# Input.net
KiCad netlist of a schematic drawn in Altium Designer
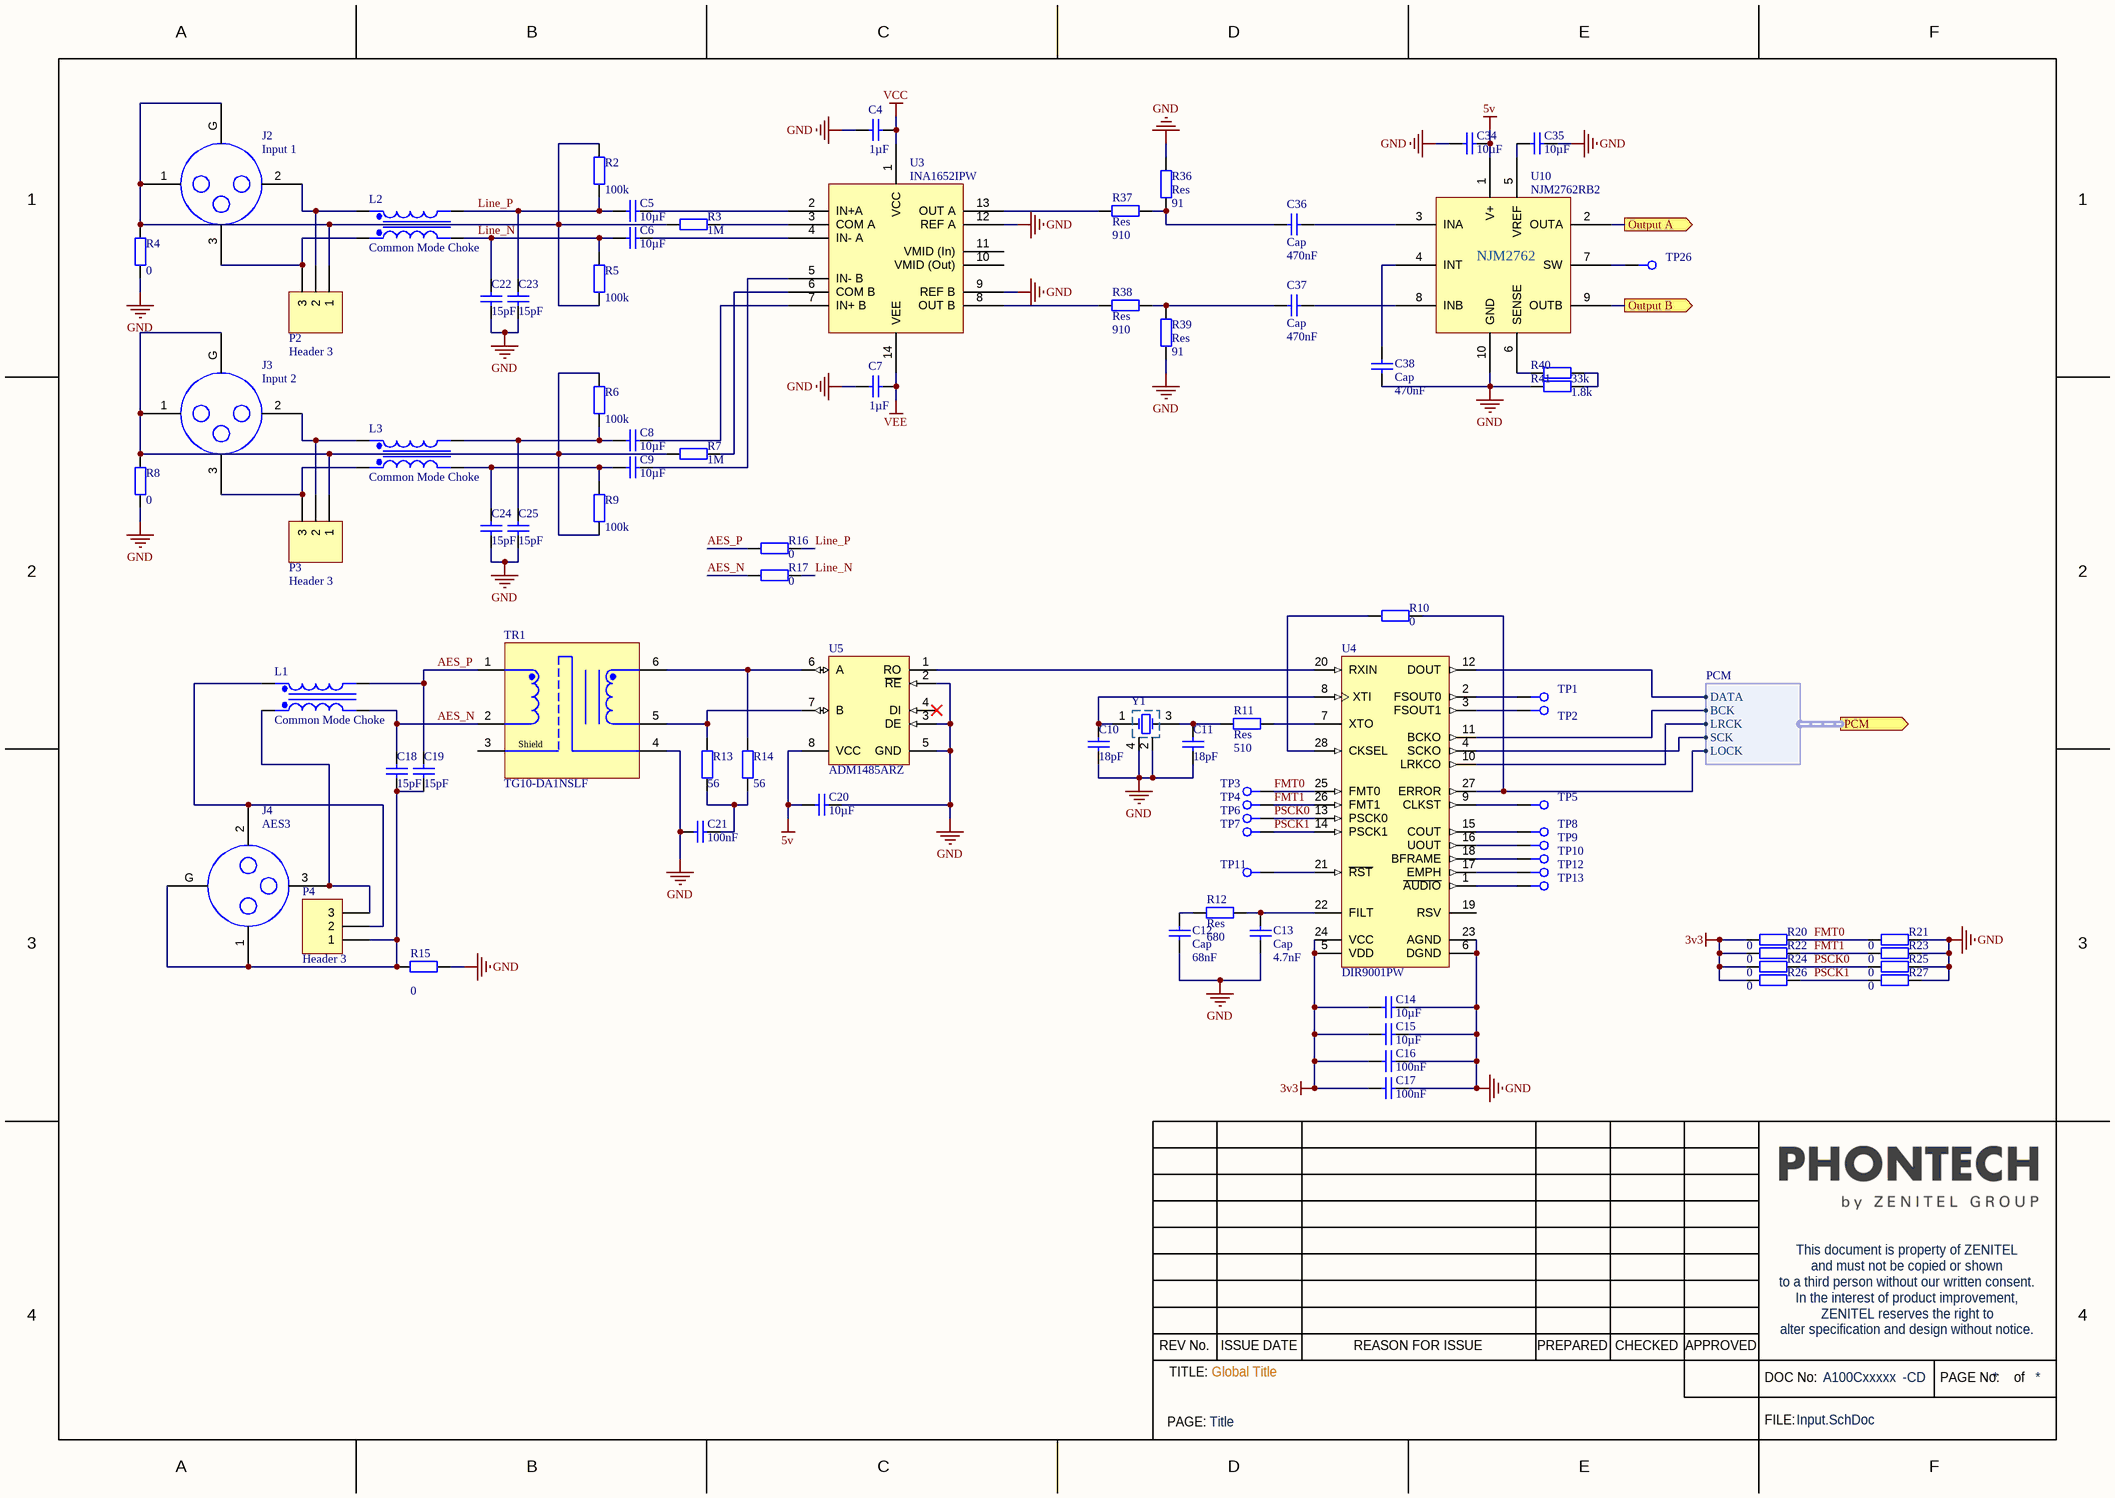
[diagram p0: Input.SchDoc]

(export (version "E")
  (design (tool "Eeschema 10.0.6"))
  (components
    (comp (ref "C4")
      (value "1µF")
      (footprint "CAPC3225N")
      (description "Chip cap 1uF 50v X7R 1210")
      (fields (field (name "TOLERANCE") "10%") (field (name "ZENITEL PARTNUMBER") "4000084277"))
      (libsource (lib "Zenitel Concord PRO Vault") (part "Capacitor-IEC"))
    )
    (comp (ref "C5")
      (value "10µF")
      (footprint "CAPC5750N")
      (description "10UF, 100V, X7S, 2220")
      (fields (field (name "TOLERANCE") "100%") (field (name "VOLTAGE") "100V"))
      (libsource (lib "Zenitel Concord PRO Vault") (part "Capacitor-IEC"))
    )
    (comp (ref "C6")
      (value "10µF")
      (footprint "CAPC5750N")
      (description "10UF, 100V, X7S, 2220")
      (fields (field (name "TOLERANCE") "100%") (field (name "VOLTAGE") "100V"))
      (libsource (lib "Zenitel Concord PRO Vault") (part "Capacitor-IEC"))
    )
    (comp (ref "C7")
      (value "1µF")
      (footprint "CAPC3225N")
      (description "Chip cap 1uF 50v X7R 1210")
      (fields (field (name "TOLERANCE") "10%") (field (name "ZENITEL PARTNUMBER") "4000084277"))
      (libsource (lib "Zenitel Concord PRO Vault") (part "Capacitor-IEC"))
    )
    (comp (ref "C8")
      (value "10µF")
      (footprint "CAPC5750N")
      (description "10UF, 100V, X7S, 2220")
      (fields (field (name "TOLERANCE") "100%") (field (name "VOLTAGE") "100V"))
      (libsource (lib "Zenitel Concord PRO Vault") (part "Capacitor-IEC"))
    )
    (comp (ref "C9")
      (value "10µF")
      (footprint "CAPC5750N")
      (description "10UF, 100V, X7S, 2220")
      (fields (field (name "TOLERANCE") "100%") (field (name "VOLTAGE") "100V"))
      (libsource (lib "Zenitel Concord PRO Vault") (part "Capacitor-IEC"))
    )
    (comp (ref "C10")
      (value "18pF")
      (footprint "CAPC1005X56X25NL10T15")
      (description "Chip cap 18p 50V - 0402")
      (fields (field (name "TOLERANCE") "5%") (field (name "ZENITEL PARTNUMBER") "4000080916"))
      (libsource (lib "Zenitel Concord PRO Vault") (part "Capacitor-IEC"))
    )
    (comp (ref "C11")
      (value "18pF")
      (footprint "CAPC1005X56X25NL10T15")
      (description "Chip cap 18p 50V - 0402")
      (fields (field (name "TOLERANCE") "5%") (field (name "ZENITEL PARTNUMBER") "4000080916"))
      (libsource (lib "Zenitel Concord PRO Vault") (part "Capacitor-IEC"))
    )
    (comp (ref "C12")
      (value "Cap")
      (footprint "CAPC1005X56X25NL10T15")
      (description "Chip cap 68n 10V - 0402")
      (fields
        (field (name "ALTIUM_VALUE") "68nF")
        (field (name "VOLTAGE") "10V")
        (field (name "TOLERANCE") "100%")
      )
      (libsource (lib "Zenitel Concord PRO Vault") (part "Capacitor-IEC"))
    )
    (comp (ref "C13")
      (value "Cap")
      (footprint "CAPC1005X56X25NL10T15")
      (description "Chip cap 4700p 50V - 0402")
      (fields
        (field (name "ALTIUM_VALUE") "4.7nF")
        (field (name "ZENITEL PARTNUMBER") "4000080940")
        (field (name "VOLTAGE") "50V")
      )
      (libsource (lib "Zenitel Concord PRO Vault") (part "Capacitor-IEC"))
    )
    (comp (ref "C14")
      (value "10µF")
      (footprint "CAPC2013X140X50NL20T25")
      (description "CR0805 10u 10V X7R 10% h=1.25mm")
      (fields (field (name "TOLERANCE") "10%") (field (name "VOLTAGE") "10V"))
      (libsource (lib "Zenitel Concord PRO Vault") (part "Capacitor-IEC"))
    )
    (comp (ref "C15")
      (value "10µF")
      (footprint "CAPC2013X140X50NL20T25")
      (description "CR0805 10u 10V X7R 10% h=1.25mm")
      (fields (field (name "TOLERANCE") "10%") (field (name "VOLTAGE") "10V"))
      (libsource (lib "Zenitel Concord PRO Vault") (part "Capacitor-IEC"))
    )
    (comp (ref "C16")
      (value "100nF")
      (footprint "CAPC1005X56X25NL10T15")
      (description "Chip cap  100n 10V - 0402  X7R")
      (fields (field (name "TOLERANCE") "10%") (field (name "VOLTAGE") "10V"))
      (libsource (lib "Zenitel Concord PRO Vault") (part "Capacitor-IEC"))
    )
    (comp (ref "C17")
      (value "100nF")
      (footprint "CAPC1005X56X25NL10T15")
      (description "Chip cap  100n 10V - 0402  X7R")
      (fields (field (name "TOLERANCE") "10%") (field (name "VOLTAGE") "10V"))
      (libsource (lib "Zenitel Concord PRO Vault") (part "Capacitor-IEC"))
    )
    (comp (ref "C18")
      (value "15pF")
      (footprint "CAPC1005X56X25NL10T15")
      (description "Chip cap 15pF 50V NP0 - 0402")
      (fields (field (name "TOLERANCE") "1%") (field (name "ZENITEL PARTNUMBER") "EFSMD17120"))
      (libsource (lib "Zenitel Concord PRO Vault") (part "Capacitor-IEC"))
    )
    (comp (ref "C19")
      (value "15pF")
      (footprint "CAPC1005X56X25NL10T15")
      (description "Chip cap 15pF 50V NP0 - 0402")
      (fields (field (name "TOLERANCE") "1%") (field (name "ZENITEL PARTNUMBER") "EFSMD17120"))
      (libsource (lib "Zenitel Concord PRO Vault") (part "Capacitor-IEC"))
    )
    (comp (ref "C20")
      (value "10µF")
      (footprint "CAPC2013X140X50NL20T25")
      (description "CR0805 10u 10V X7R 10% h=1.25mm")
      (fields (field (name "TOLERANCE") "10%") (field (name "VOLTAGE") "10V"))
      (libsource (lib "Zenitel Concord PRO Vault") (part "Capacitor-IEC"))
    )
    (comp (ref "C21")
      (value "100nF")
      (footprint "CAPC1608X90X35NL15T15")
      (description "Chip cap  100n 50V X7R - 0603")
      (fields (field (name "ZENITEL PARTNUMBER") "4000084734") (field (name "TOLERANCE") "10%"))
      (libsource (lib "Zenitel Concord PRO Vault") (part "Capacitor-IEC"))
    )
    (comp (ref "C22")
      (value "15pF")
      (footprint "CAPC1005X56X25NL10T15")
      (description "Chip cap 15pF 50V NP0 - 0402")
      (fields (field (name "TOLERANCE") "1%") (field (name "ZENITEL PARTNUMBER") "EFSMD17120"))
      (libsource (lib "Zenitel Concord PRO Vault") (part "Capacitor-IEC"))
    )
    (comp (ref "C23")
      (value "15pF")
      (footprint "CAPC1005X56X25NL10T15")
      (description "Chip cap 15pF 50V NP0 - 0402")
      (fields (field (name "TOLERANCE") "1%") (field (name "ZENITEL PARTNUMBER") "EFSMD17120"))
      (libsource (lib "Zenitel Concord PRO Vault") (part "Capacitor-IEC"))
    )
    (comp (ref "C24")
      (value "15pF")
      (footprint "CAPC1005X56X25NL10T15")
      (description "Chip cap 15pF 50V NP0 - 0402")
      (fields (field (name "TOLERANCE") "1%") (field (name "ZENITEL PARTNUMBER") "EFSMD17120"))
      (libsource (lib "Zenitel Concord PRO Vault") (part "Capacitor-IEC"))
    )
    (comp (ref "C25")
      (value "15pF")
      (footprint "CAPC1005X56X25NL10T15")
      (description "Chip cap 15pF 50V NP0 - 0402")
      (fields (field (name "TOLERANCE") "1%") (field (name "ZENITEL PARTNUMBER") "EFSMD17120"))
      (libsource (lib "Zenitel Concord PRO Vault") (part "Capacitor-IEC"))
    )
    (comp (ref "C34")
      (value "10µF")
      (footprint "CAPC2013X140X50NL20T25")
      (description "CR0805 10u 10V X7R 10% h=1.25mm")
      (fields (field (name "TOLERANCE") "10%") (field (name "VOLTAGE") "10V"))
      (libsource (lib "Zenitel Concord PRO Vault") (part "Capacitor-IEC"))
    )
    (comp (ref "C35")
      (value "10µF")
      (footprint "CAPC2013X140X50NL20T25")
      (description "CR0805 10u 10V X7R 10% h=1.25mm")
      (fields (field (name "TOLERANCE") "10%") (field (name "VOLTAGE") "10V"))
      (libsource (lib "Zenitel Concord PRO Vault") (part "Capacitor-IEC"))
    )
    (comp (ref "C36")
      (value "Cap")
      (footprint "CAPC1608X90X35NL15T15")
      (description "Chip cap 470nF 16V X7R - 0603")
      (fields
        (field (name "ALTIUM_VALUE") "470nF")
        (field (name "VOLTAGE") "16V")
        (field (name "ZENITEL PARTNUMBER") "EFSMD16664")
      )
      (libsource (lib "Zenitel Concord PRO Vault") (part "Capacitor-IEC"))
    )
    (comp (ref "C37")
      (value "Cap")
      (footprint "CAPC1608X90X35NL15T15")
      (description "Chip cap 470nF 16V X7R - 0603")
      (fields
        (field (name "ALTIUM_VALUE") "470nF")
        (field (name "VOLTAGE") "16V")
        (field (name "ZENITEL PARTNUMBER") "EFSMD16664")
      )
      (libsource (lib "Zenitel Concord PRO Vault") (part "Capacitor-IEC"))
    )
    (comp (ref "C38")
      (value "Cap")
      (footprint "CAPC1608X90X35NL15T15")
      (description "Chip cap 470nF 16V X7R - 0603")
      (fields
        (field (name "ALTIUM_VALUE") "470nF")
        (field (name "VOLTAGE") "16V")
        (field (name "ZENITEL PARTNUMBER") "EFSMD16664")
      )
      (libsource (lib "Zenitel Concord PRO Vault") (part "Capacitor-IEC"))
    )
    (comp (ref "J2")
      (value "Input 1")
      (footprint "NC3FAH2")
      (description "NC3FAH2 3pole female XLR 90deg")
      (fields (field (name "ZENITEL PARTNUMBER") "4000083398"))
      (libsource (lib "Zenitel Concord PRO Vault") (part "NC3FAH2"))
    )
    (comp (ref "J3")
      (value "Input 2")
      (footprint "NC3FAH2")
      (description "NC3FAH2 3pole female XLR 90deg")
      (fields (field (name "ZENITEL PARTNUMBER") "4000083398"))
      (libsource (lib "Zenitel Concord PRO Vault") (part "NC3FAH2"))
    )
    (comp (ref "J4")
      (value "AES3")
      (footprint "NC3FAH2")
      (description "NC3FAH2 3pole female XLR 90deg")
      (fields (field (name "ZENITEL PARTNUMBER") "4000083398"))
      (libsource (lib "Zenitel Concord PRO Vault") (part "NC3FAH2"))
    )
    (comp (ref "L1")
      (value "Common Mode Choke")
      (footprint "WE-CNSW-1206")
      (description "WE-CNSW SMD Common Mode Line Filter")
      (fields (field (name "ZENITEL PARTNUMBER") "4000086128"))
      (libsource (lib "Zenitel Concord PRO Vault") (part "Common Mode Choke"))
    )
    (comp (ref "L2")
      (value "Common Mode Choke")
      (footprint "WE-CNSW-1206")
      (description "WE-CNSW SMD Common Mode Line Filter")
      (fields (field (name "ZENITEL PARTNUMBER") "4000086128"))
      (libsource (lib "Zenitel Concord PRO Vault") (part "Common Mode Choke"))
    )
    (comp (ref "L3")
      (value "Common Mode Choke")
      (footprint "WE-CNSW-1206")
      (description "WE-CNSW SMD Common Mode Line Filter")
      (fields (field (name "ZENITEL PARTNUMBER") "4000086128"))
      (libsource (lib "Zenitel Concord PRO Vault") (part "Common Mode Choke"))
    )
    (comp (ref "P2")
      (value "Header 3")
      (footprint "MTA-100-3P")
      (description "MTA-100-3P 3-pin header")
      (fields (field (name "ZENITEL PARTNUMBER") "4000085467"))
      (libsource (lib "Zenitel Concord PRO Vault") (part "Header 3"))
    )
    (comp (ref "P3")
      (value "Header 3")
      (footprint "MTA-100-3P")
      (description "MTA-100-3P 3-pin header")
      (fields (field (name "ZENITEL PARTNUMBER") "4000085467"))
      (libsource (lib "Zenitel Concord PRO Vault") (part "Header 3"))
    )
    (comp (ref "P4")
      (value "Header 3")
      (footprint "MTA-100-3P")
      (description "MTA-100-3P 3-pin header")
      (fields (field (name "ZENITEL PARTNUMBER") "4000085467"))
      (libsource (lib "") (part "Header 3_1"))
    )
    (comp (ref "R2")
      (value "100k")
      (footprint "RESC1005X40X25NL05T05")
      (description "Chip resistor 100K - 0402")
      (fields (field (name "POWER") "62.5mW") (field (name "ZENITEL PARTNUMBER") "4000081112"))
      (libsource (lib "Zenitel Concord PRO Vault") (part "Resistor-IEC"))
    )
    (comp (ref "R3")
      (value "1M")
      (footprint "RESC1005X40X25NL05T05")
      (description "Chip resistor 1M 1% - 0402")
      (fields (field (name "VOLTAGE") "50V") (field (name "POWER") "62.5mW"))
      (libsource (lib "") (part "Resistor-IEC_1"))
    )
    (comp (ref "R4")
      (value "0")
      (footprint "RESC3216X60X45NL10T20")
      (description "0R 1206")
      (fields (field (name "ZENITEL PARTNUMBER") "4000085059") (field (name "POWER") "250mW"))
      (libsource (lib "Zenitel Concord PRO Vault") (part "Resistor-IEC"))
    )
    (comp (ref "R5")
      (value "100k")
      (footprint "RESC1005X40X25NL05T05")
      (description "Chip resistor 100K - 0402")
      (fields (field (name "POWER") "62.5mW") (field (name "ZENITEL PARTNUMBER") "4000081112"))
      (libsource (lib "Zenitel Concord PRO Vault") (part "Resistor-IEC"))
    )
    (comp (ref "R6")
      (value "100k")
      (footprint "RESC1005X40X25NL05T05")
      (description "Chip resistor 100K - 0402")
      (fields (field (name "POWER") "62.5mW") (field (name "ZENITEL PARTNUMBER") "4000081112"))
      (libsource (lib "Zenitel Concord PRO Vault") (part "Resistor-IEC"))
    )
    (comp (ref "R7")
      (value "1M")
      (footprint "RESC1005X40X25NL05T05")
      (description "Chip resistor 1M 1% - 0402")
      (fields (field (name "VOLTAGE") "50V") (field (name "POWER") "62.5mW"))
      (libsource (lib "") (part "Resistor-IEC_1"))
    )
    (comp (ref "R8")
      (value "0")
      (footprint "RESC3216X60X45NL10T20")
      (description "0R 1206")
      (fields (field (name "ZENITEL PARTNUMBER") "4000085059") (field (name "POWER") "250mW"))
      (libsource (lib "Zenitel Concord PRO Vault") (part "Resistor-IEC"))
    )
    (comp (ref "R9")
      (value "100k")
      (footprint "RESC1005X40X25NL05T05")
      (description "Chip resistor 100K - 0402")
      (fields (field (name "POWER") "62.5mW") (field (name "ZENITEL PARTNUMBER") "4000081112"))
      (libsource (lib "Zenitel Concord PRO Vault") (part "Resistor-IEC"))
    )
    (comp (ref "R10")
      (value "0")
      (footprint "RESC1005X40X25NL05T05")
      (description "Chip resistor 0R - 0402")
      (fields (field (name "POWER") "62.5mW") (field (name "TOLERANCE") "1%"))
      (libsource (lib "") (part "Resistor-IEC_1"))
    )
    (comp (ref "R11")
      (value "Res")
      (footprint "RESC1005X40X25NL05T05")
      (description "Chip resistor 0402 - 510R 1%")
      (fields
        (field (name "ALTIUM_VALUE") "510")
        (field (name "TOLERANCE") "1%")
        (field (name "ZENITEL PARTNUMBER") "4000088250")
      )
      (libsource (lib "") (part "Resistor-IEC_1"))
    )
    (comp (ref "R12")
      (value "Res")
      (footprint "RESC1005X40X25NL05T05")
      (description "Chip resistor 680R - 0402")
      (fields
        (field (name "ALTIUM_VALUE") "680")
        (field (name "POWER") "62.5mW")
        (field (name "TOLERANCE") "1%")
      )
      (libsource (lib "") (part "Resistor-IEC_1"))
    )
    (comp (ref "R13")
      (value "56")
      (footprint "RESC1609X50X30NL10T20")
      (description "CR 0603 56R 5%")
      (fields (field (name "ZENITEL PARTNUMBER") "4000098393") (field (name "POWER") "100mW"))
      (libsource (lib "Zenitel Concord PRO Vault") (part "Resistor-IEC"))
    )
    (comp (ref "R14")
      (value "56")
      (footprint "RESC1609X50X30NL10T20")
      (description "CR 0603 56R 5%")
      (fields (field (name "ZENITEL PARTNUMBER") "4000098393") (field (name "POWER") "100mW"))
      (libsource (lib "Zenitel Concord PRO Vault") (part "Resistor-IEC"))
    )
    (comp (ref "R15")
      (value "0")
      (footprint "RESC3216X60X45NL10T20")
      (description "0R 1206")
      (fields (field (name "ZENITEL PARTNUMBER") "4000085059") (field (name "POWER") "250mW"))
      (libsource (lib "") (part "Resistor-IEC_3"))
    )
    (comp (ref "R16")
      (value "0")
      (footprint "RESC3216X60X45NL10T20")
      (description "0R 1206")
      (fields (field (name "ZENITEL PARTNUMBER") "4000085059") (field (name "POWER") "250mW"))
      (libsource (lib "") (part "Resistor-IEC_2"))
    )
    (comp (ref "R17")
      (value "0")
      (footprint "RESC3216X60X45NL10T20")
      (description "0R 1206")
      (fields (field (name "ZENITEL PARTNUMBER") "4000085059") (field (name "POWER") "250mW"))
      (libsource (lib "") (part "Resistor-IEC_2"))
    )
    (comp (ref "R20")
      (value "0")
      (footprint "RESC1005X40X25NL05T05")
      (description "Chip resistor 0R - 0402")
      (fields (field (name "POWER") "62.5mW") (field (name "TOLERANCE") "1%"))
      (libsource (lib "") (part "Resistor-IEC_1"))
    )
    (comp (ref "R21")
      (value "0")
      (footprint "RESC1005X40X25NL05T05")
      (description "Chip resistor 0R - 0402")
      (fields (field (name "POWER") "62.5mW") (field (name "TOLERANCE") "1%"))
      (libsource (lib "") (part "Resistor-IEC_1"))
    )
    (comp (ref "R22")
      (value "0")
      (footprint "RESC1005X40X25NL05T05")
      (description "Chip resistor 0R - 0402")
      (fields (field (name "POWER") "62.5mW") (field (name "TOLERANCE") "1%"))
      (libsource (lib "") (part "Resistor-IEC_1"))
    )
    (comp (ref "R23")
      (value "0")
      (footprint "RESC1005X40X25NL05T05")
      (description "Chip resistor 0R - 0402")
      (fields (field (name "POWER") "62.5mW") (field (name "TOLERANCE") "1%"))
      (libsource (lib "") (part "Resistor-IEC_1"))
    )
    (comp (ref "R24")
      (value "0")
      (footprint "RESC1005X40X25NL05T05")
      (description "Chip resistor 0R - 0402")
      (fields (field (name "POWER") "62.5mW") (field (name "TOLERANCE") "1%"))
      (libsource (lib "") (part "Resistor-IEC_1"))
    )
    (comp (ref "R25")
      (value "0")
      (footprint "RESC1005X40X25NL05T05")
      (description "Chip resistor 0R - 0402")
      (fields (field (name "POWER") "62.5mW") (field (name "TOLERANCE") "1%"))
      (libsource (lib "") (part "Resistor-IEC_1"))
    )
    (comp (ref "R26")
      (value "0")
      (footprint "RESC1005X40X25NL05T05")
      (description "Chip resistor 0R - 0402")
      (fields (field (name "POWER") "62.5mW") (field (name "TOLERANCE") "1%"))
      (libsource (lib "") (part "Resistor-IEC_1"))
    )
    (comp (ref "R27")
      (value "0")
      (footprint "RESC1005X40X25NL05T05")
      (description "Chip resistor 0R - 0402")
      (fields (field (name "POWER") "62.5mW") (field (name "TOLERANCE") "1%"))
      (libsource (lib "") (part "Resistor-IEC_1"))
    )
    (comp (ref "R36")
      (value "Res")
      (footprint "RESC1609X50X30NL10T20")
      (description "CR 0603 91R 1%")
      (fields
        (field (name "ALTIUM_VALUE") "91")
        (field (name "POWER") "100mW")
        (field (name "ZENITEL PARTNUMBER") "4000098398")
      )
      (libsource (lib "Zenitel Concord PRO Vault") (part "Resistor-IEC"))
    )
    (comp (ref "R37")
      (value "Res")
      (footprint "RESC1609X50X30NL10T20")
      (description "CR 0603 910R 1%")
      (fields
        (field (name "ALTIUM_VALUE") "910")
        (field (name "TOLERANCE") "1%")
        (field (name "ZENITEL PARTNUMBER") "4000098422")
      )
      (libsource (lib "") (part "Resistor-IEC_1"))
    )
    (comp (ref "R38")
      (value "Res")
      (footprint "RESC1609X50X30NL10T20")
      (description "CR 0603 910R 1%")
      (fields
        (field (name "ALTIUM_VALUE") "910")
        (field (name "TOLERANCE") "1%")
        (field (name "ZENITEL PARTNUMBER") "4000098422")
      )
      (libsource (lib "") (part "Resistor-IEC_1"))
    )
    (comp (ref "R39")
      (value "Res")
      (footprint "RESC1609X50X30NL10T20")
      (description "CR 0603 91R 1%")
      (fields
        (field (name "ALTIUM_VALUE") "91")
        (field (name "POWER") "100mW")
        (field (name "ZENITEL PARTNUMBER") "4000098398")
      )
      (libsource (lib "Zenitel Concord PRO Vault") (part "Resistor-IEC"))
    )
    (comp (ref "R40")
      (value "33k")
      (footprint "RESC1005X40X25NL05T05")
      (description "Chip resistor 33K - 0402")
      (fields (field (name "ZENITEL PARTNUMBER") "4000081106") (field (name "TOLERANCE") "1%"))
      (libsource (lib "") (part "Resistor-IEC_2"))
    )
    (comp (ref "R41")
      (value "1.8k")
      (footprint "RESC1005X40X25NL05T05")
      (description "Chip resistor 1K8 - 0402")
      (fields (field (name "ZENITEL PARTNUMBER") "4000081091") (field (name "VOLTAGE") "50V"))
      (libsource (lib "") (part "Resistor-IEC_1"))
    )
    (comp (ref "TP1")
      (value "TP Ø1.27MM")
      (footprint "TP_1.27MM")
      (description "Test Point, copper pad, 1.27mm diameter")
      (libsource (lib "Zenitel Concord PRO Vault") (part "Symbol"))
    )
    (comp (ref "TP2")
      (value "TP Ø1.27MM")
      (footprint "TP_1.27MM")
      (description "Test Point, copper pad, 1.27mm diameter")
      (libsource (lib "Zenitel Concord PRO Vault") (part "Symbol"))
    )
    (comp (ref "TP3")
      (value "TP Ø1.27MM")
      (footprint "TP_1.27MM")
      (description "Test Point, copper pad, 1.27mm diameter")
      (libsource (lib "Zenitel Concord PRO Vault") (part "Symbol"))
    )
    (comp (ref "TP4")
      (value "TP Ø1.27MM")
      (footprint "TP_1.27MM")
      (description "Test Point, copper pad, 1.27mm diameter")
      (libsource (lib "Zenitel Concord PRO Vault") (part "Symbol"))
    )
    (comp (ref "TP5")
      (value "TP Ø1.27MM")
      (footprint "TP_1.27MM")
      (description "Test Point, copper pad, 1.27mm diameter")
      (libsource (lib "Zenitel Concord PRO Vault") (part "Symbol"))
    )
    (comp (ref "TP6")
      (value "TP Ø1.27MM")
      (footprint "TP_1.27MM")
      (description "Test Point, copper pad, 1.27mm diameter")
      (libsource (lib "Zenitel Concord PRO Vault") (part "Symbol"))
    )
    (comp (ref "TP7")
      (value "TP Ø1.27MM")
      (footprint "TP_1.27MM")
      (description "Test Point, copper pad, 1.27mm diameter")
      (libsource (lib "Zenitel Concord PRO Vault") (part "Symbol"))
    )
    (comp (ref "TP8")
      (value "TP Ø1.27MM")
      (footprint "TP_1.27MM")
      (description "Test Point, copper pad, 1.27mm diameter")
      (libsource (lib "Zenitel Concord PRO Vault") (part "Symbol"))
    )
    (comp (ref "TP9")
      (value "TP Ø1.27MM")
      (footprint "TP_1.27MM")
      (description "Test Point, copper pad, 1.27mm diameter")
      (libsource (lib "Zenitel Concord PRO Vault") (part "Symbol"))
    )
    (comp (ref "TP10")
      (value "TP Ø1.27MM")
      (footprint "TP_1.27MM")
      (description "Test Point, copper pad, 1.27mm diameter")
      (libsource (lib "Zenitel Concord PRO Vault") (part "Symbol"))
    )
    (comp (ref "TP11")
      (value "TP Ø1.27MM")
      (footprint "TP_1.27MM")
      (description "Test Point, copper pad, 1.27mm diameter")
      (libsource (lib "Zenitel Concord PRO Vault") (part "Symbol"))
    )
    (comp (ref "TP12")
      (value "TP Ø1.27MM")
      (footprint "TP_1.27MM")
      (description "Test Point, copper pad, 1.27mm diameter")
      (libsource (lib "Zenitel Concord PRO Vault") (part "Symbol"))
    )
    (comp (ref "TP13")
      (value "TP Ø1.27MM")
      (footprint "TP_1.27MM")
      (description "Test Point, copper pad, 1.27mm diameter")
      (libsource (lib "Zenitel Concord PRO Vault") (part "Symbol"))
    )
    (comp (ref "TP26")
      (value "TP Ø1.27MM")
      (footprint "TP_1.27MM")
      (description "Test Point, copper pad, 1.27mm diameter")
      (libsource (lib "Zenitel Concord PRO Vault") (part "Symbol"))
    )
    (comp (ref "TR1")
      (value "TG10-DA1NSLF")
      (footprint "TG10-DA1NSLF-Footprint-1")
      (description "Audio Transformers / Signal Transformers ISO MOD GullWng Sgl Audio w/ shield 6pin")
      (libsource (lib "Zenitel Concord PRO Vault") (part "TG10-DA1NSLF"))
    )
    (comp (ref "U3")
      (value "INA1652IPW")
      (footprint "SOP65P640X120-14N")
      (description "SoundPlus™ high common-mode rejection (91-dB), low THD+N (-120-dB) dual differential line receiver")
      (libsource (lib "Zenitel Concord PRO Vault") (part "INA1652IPW"))
    )
    (comp (ref "U4")
      (value "DIR9001PW")
      (footprint "PW0028A_N")
      (fields (field (name "MANUFACTURER") "Texas Instruments"))
      (libsource (lib "Altium Content Vault") (part "TI-DIR9001-TSSOP_PW-28"))
    )
    (comp (ref "U5")
      (value "ADM1485ARZ")
      (footprint "ADI-R-8_M")
      (fields (field (name "MANUFACTURER") "Analog Devices"))
      (libsource (lib "Altium Content Vault") (part "ADI-ADM3483_5-R-8"))
    )
    (comp (ref "U10")
      (value "NJM2762RB2")
      (footprint "SOP50P490X110-10N")
      (description "2-Channel Audio Limiter")
      (libsource (lib "Zenitel Concord PRO Vault") (part "NJM2762"))
    )
    (comp (ref "Y1")
      (value "Crystal4")
      (footprint "XTAL-5x3.2MM")
      (description "Crystal 24.576MHZ 18pF 5X3.2mm")
      (fields (field (name "ZENITEL PARTNUMBER") "4000086516"))
      (libsource (lib "Zenitel Concord PRO Vault") (part "Crystal4"))
    )
  )
  (nets
    (net (code "2") (name "/AES_N") (class "Default")
      (node (ref "C18") (pin "2") (pinfunction "2_2") (pintype "passive"))
      (node (ref "L1") (pin "4") (pinfunction "4_4") (pintype "passive"))
      (node (ref "R17") (pin "2") (pinfunction "2_2") (pintype "passive"))
      (node (ref "TR1") (pin "2") (pinfunction "2_2") (pintype "passive"))
    )
    (net (code "3") (name "/AES_P") (class "Default")
      (node (ref "C19") (pin "2") (pinfunction "2_2") (pintype "passive"))
      (node (ref "L1") (pin "3") (pinfunction "3_3") (pintype "passive"))
      (node (ref "R16") (pin "2") (pinfunction "2_2") (pintype "passive"))
      (node (ref "TR1") (pin "1") (pinfunction "1_1") (pintype "passive"))
    )
    (net (code "4") (name "/BCK") (class "Default")
      (node (ref "U4") (pin "11") (pinfunction "BCKO_11") (pintype "output"))
    )
    (net (code "5") (name "/DATA") (class "Default")
      (node (ref "U4") (pin "12") (pinfunction "DOUT_12") (pintype "output"))
    )
    (net (code "6") (name "/FMT0") (class "Default")
      (node (ref "R20") (pin "2") (pinfunction "2_2") (pintype "passive"))
      (node (ref "R21") (pin "1") (pinfunction "1_1") (pintype "passive"))
      (node (ref "TP3") (pin "1") (pinfunction "1_1") (pintype "passive"))
      (node (ref "U4") (pin "25") (pinfunction "FMT0_25") (pintype "input"))
    )
    (net (code "7") (name "/FMT1") (class "Default")
      (node (ref "R22") (pin "2") (pinfunction "2_2") (pintype "passive"))
      (node (ref "R23") (pin "1") (pinfunction "1_1") (pintype "passive"))
      (node (ref "TP4") (pin "1") (pinfunction "1_1") (pintype "passive"))
      (node (ref "U4") (pin "26") (pinfunction "FMT1_26") (pintype "input"))
    )
    (net (code "8") (name "/LOCK") (class "Default")
      (node (ref "R10") (pin "2") (pinfunction "2_2") (pintype "passive"))
      (node (ref "U4") (pin "27") (pinfunction "ERROR_27") (pintype "output"))
    )
    (net (code "9") (name "/LRCK") (class "Default")
      (node (ref "U4") (pin "10") (pinfunction "LRKCO_10") (pintype "output"))
    )
    (net (code "10") (name "/Line_N") (class "Default")
      (node (ref "C22") (pin "2") (pinfunction "2_2") (pintype "passive"))
      (node (ref "C6") (pin "1") (pinfunction "1_1") (pintype "passive"))
      (node (ref "L2") (pin "4") (pinfunction "4_4") (pintype "passive"))
      (node (ref "R17") (pin "1") (pinfunction "1_1") (pintype "passive"))
      (node (ref "R5") (pin "2") (pinfunction "2_2") (pintype "passive"))
    )
    (net (code "11") (name "/Line_P") (class "Default")
      (node (ref "C23") (pin "2") (pinfunction "2_2") (pintype "passive"))
      (node (ref "C5") (pin "1") (pinfunction "1_1") (pintype "passive"))
      (node (ref "L2") (pin "3") (pinfunction "3_3") (pintype "passive"))
      (node (ref "R16") (pin "1") (pinfunction "1_1") (pintype "passive"))
      (node (ref "R2") (pin "1") (pinfunction "1_1") (pintype "passive"))
    )
    (net (code "12") (name "/Output A") (class "Default")
      (node (ref "U10") (pin "2") (pinfunction "OUTA_2") (pintype "passive"))
    )
    (net (code "13") (name "/Output B") (class "Default")
      (node (ref "U10") (pin "9") (pinfunction "OUTB_9") (pintype "passive"))
    )
    (net (code "14") (name "/PSCK0") (class "Default")
      (node (ref "R24") (pin "2") (pinfunction "2_2") (pintype "passive"))
      (node (ref "R25") (pin "1") (pinfunction "1_1") (pintype "passive"))
      (node (ref "TP6") (pin "1") (pinfunction "1_1") (pintype "passive"))
      (node (ref "U4") (pin "13") (pinfunction "PSCK0_13") (pintype "input"))
    )
    (net (code "15") (name "/PSCK1") (class "Default")
      (node (ref "R26") (pin "2") (pinfunction "2_2") (pintype "passive"))
      (node (ref "R27") (pin "1") (pinfunction "1_1") (pintype "passive"))
      (node (ref "TP7") (pin "1") (pinfunction "1_1") (pintype "passive"))
      (node (ref "U4") (pin "14") (pinfunction "PSCK1_14") (pintype "input"))
    )
    (net (code "16") (name "/SCK") (class "Default")
      (node (ref "U4") (pin "4") (pinfunction "SCKO_4") (pintype "output"))
    )
    (net (code "18") (name "3v3") (class "Default")
      (node (ref "C14") (pin "2") (pinfunction "2_2") (pintype "passive"))
      (node (ref "C15") (pin "2") (pinfunction "2_2") (pintype "passive"))
      (node (ref "C16") (pin "1") (pinfunction "1_1") (pintype "passive"))
      (node (ref "C17") (pin "1") (pinfunction "1_1") (pintype "passive"))
      (node (ref "R20") (pin "1") (pinfunction "1_1") (pintype "passive"))
      (node (ref "R22") (pin "1") (pinfunction "1_1") (pintype "passive"))
      (node (ref "R24") (pin "1") (pinfunction "1_1") (pintype "passive"))
      (node (ref "R26") (pin "1") (pinfunction "1_1") (pintype "passive"))
      (node (ref "U4") (pin "24") (pinfunction "VCC_24") (pintype "power_in"))
      (node (ref "U4") (pin "5") (pinfunction "VDD_5") (pintype "power_in"))
    )
    (net (code "19") (name "5v") (class "Default")
      (node (ref "C20") (pin "2") (pinfunction "2_2") (pintype "passive"))
      (node (ref "C34") (pin "1") (pinfunction "1_1") (pintype "passive"))
      (node (ref "U10") (pin "1") (pinfunction "V+_1") (pintype "passive"))
      (node (ref "U5") (pin "8") (pinfunction "VCC_8") (pintype "power_in"))
    )
    (net (code "20") (name "GND") (class "Default")
      (node (ref "C10") (pin "1") (pinfunction "1_1") (pintype "passive"))
      (node (ref "C11") (pin "1") (pinfunction "1_1") (pintype "passive"))
      (node (ref "C12") (pin "1") (pinfunction "1_1") (pintype "passive"))
      (node (ref "C13") (pin "1") (pinfunction "1_1") (pintype "passive"))
      (node (ref "C14") (pin "1") (pinfunction "1_1") (pintype "passive"))
      (node (ref "C15") (pin "1") (pinfunction "1_1") (pintype "passive"))
      (node (ref "C16") (pin "2") (pinfunction "2_2") (pintype "passive"))
      (node (ref "C17") (pin "2") (pinfunction "2_2") (pintype "passive"))
      (node (ref "C20") (pin "1") (pinfunction "1_1") (pintype "passive"))
      (node (ref "C21") (pin "1") (pinfunction "1_1") (pintype "passive"))
      (node (ref "C22") (pin "1") (pinfunction "1_1") (pintype "passive"))
      (node (ref "C23") (pin "1") (pinfunction "1_1") (pintype "passive"))
      (node (ref "C24") (pin "1") (pinfunction "1_1") (pintype "passive"))
      (node (ref "C25") (pin "1") (pinfunction "1_1") (pintype "passive"))
      (node (ref "C34") (pin "2") (pinfunction "2_2") (pintype "passive"))
      (node (ref "C35") (pin "1") (pinfunction "1_1") (pintype "passive"))
      (node (ref "C38") (pin "1") (pinfunction "1_1") (pintype "passive"))
      (node (ref "C4") (pin "1") (pinfunction "1_1") (pintype "passive"))
      (node (ref "C7") (pin "1") (pinfunction "1_1") (pintype "passive"))
      (node (ref "R15") (pin "1") (pinfunction "1_1") (pintype "passive"))
      (node (ref "R21") (pin "2") (pinfunction "2_2") (pintype "passive"))
      (node (ref "R23") (pin "2") (pinfunction "2_2") (pintype "passive"))
      (node (ref "R25") (pin "2") (pinfunction "2_2") (pintype "passive"))
      (node (ref "R27") (pin "2") (pinfunction "2_2") (pintype "passive"))
      (node (ref "R36") (pin "2") (pinfunction "2_2") (pintype "passive"))
      (node (ref "R39") (pin "1") (pinfunction "1_1") (pintype "passive"))
      (node (ref "R4") (pin "1") (pinfunction "1_1") (pintype "passive"))
      (node (ref "R41") (pin "1") (pinfunction "1_1") (pintype "passive"))
      (node (ref "R8") (pin "1") (pinfunction "1_1") (pintype "passive"))
      (node (ref "TR1") (pin "4") (pinfunction "4_4") (pintype "passive"))
      (node (ref "U10") (pin "10") (pinfunction "GND_10") (pintype "passive"))
      (node (ref "U3") (pin "12") (pinfunction "REF_A_12") (pintype "passive"))
      (node (ref "U3") (pin "9") (pinfunction "REF_B_9") (pintype "passive"))
      (node (ref "U4") (pin "23") (pinfunction "AGND_23") (pintype "power_in"))
      (node (ref "U4") (pin "6") (pinfunction "DGND_6") (pintype "power_in"))
      (node (ref "U5") (pin "2") (pinfunction "~{RE}_2") (pintype "input"))
      (node (ref "U5") (pin "3") (pinfunction "DE_3") (pintype "input"))
      (node (ref "U5") (pin "5") (pinfunction "GND_5") (pintype "power_in"))
      (node (ref "Y1") (pin "2") (pinfunction "GND_2") (pintype "power_in"))
      (node (ref "Y1") (pin "4") (pinfunction "4_4") (pintype "passive"))
    )
    (net (code "21") (name "Net-(C12-Pad2)") (class "Default")
      (node (ref "C12") (pin "2") (pinfunction "2_2") (pintype "passive"))
      (node (ref "R12") (pin "1") (pinfunction "1_1") (pintype "passive"))
    )
    (net (code "22") (name "Net-(C18-Pad1)") (class "Default")
      (node (ref "C18") (pin "1") (pinfunction "1_1") (pintype "passive"))
      (node (ref "C19") (pin "1") (pinfunction "1_1") (pintype "passive"))
      (node (ref "J4") (pin "1") (pinfunction "1_1") (pintype "passive"))
      (node (ref "J4") (pin "G") (pinfunction "G_G") (pintype "passive"))
      (node (ref "P4") (pin "1") (pinfunction "1_1") (pintype "passive"))
      (node (ref "R15") (pin "2") (pinfunction "2_2") (pintype "passive"))
    )
    (net (code "23") (name "Net-(C21-Pad2)") (class "Default")
      (node (ref "C21") (pin "2") (pinfunction "2_2") (pintype "passive"))
      (node (ref "R13") (pin "1") (pinfunction "1_1") (pintype "passive"))
      (node (ref "R14") (pin "1") (pinfunction "1_1") (pintype "passive"))
    )
    (net (code "24") (name "Net-(C24-Pad2)") (class "Default")
      (node (ref "C24") (pin "2") (pinfunction "2_2") (pintype "passive"))
      (node (ref "C9") (pin "1") (pinfunction "1_1") (pintype "passive"))
      (node (ref "L3") (pin "4") (pinfunction "4_4") (pintype "passive"))
      (node (ref "R9") (pin "2") (pinfunction "2_2") (pintype "passive"))
    )
    (net (code "25") (name "Net-(C25-Pad2)") (class "Default")
      (node (ref "C25") (pin "2") (pinfunction "2_2") (pintype "passive"))
      (node (ref "C8") (pin "1") (pinfunction "1_1") (pintype "passive"))
      (node (ref "L3") (pin "3") (pinfunction "3_3") (pintype "passive"))
      (node (ref "R6") (pin "1") (pinfunction "1_1") (pintype "passive"))
    )
    (net (code "26") (name "Net-(C36-Pad1)") (class "Default")
      (node (ref "C36") (pin "1") (pinfunction "1_1") (pintype "passive"))
      (node (ref "R36") (pin "1") (pinfunction "1_1") (pintype "passive"))
      (node (ref "R37") (pin "2") (pinfunction "2_2") (pintype "passive"))
    )
    (net (code "27") (name "Net-(C37-Pad1)") (class "Default")
      (node (ref "C37") (pin "1") (pinfunction "1_1") (pintype "passive"))
      (node (ref "R38") (pin "2") (pinfunction "2_2") (pintype "passive"))
      (node (ref "R39") (pin "2") (pinfunction "2_2") (pintype "passive"))
    )
    (net (code "28") (name "Net-(J2-Pad1)") (class "Default")
      (node (ref "J2") (pin "1") (pinfunction "1_1") (pintype "passive"))
      (node (ref "J2") (pin "G") (pinfunction "G_G") (pintype "passive"))
      (node (ref "P2") (pin "1") (pinfunction "1_1") (pintype "passive"))
      (node (ref "R2") (pin "2") (pinfunction "2_2") (pintype "passive"))
      (node (ref "R3") (pin "1") (pinfunction "1_1") (pintype "passive"))
      (node (ref "R4") (pin "2") (pinfunction "2_2") (pintype "passive"))
      (node (ref "R5") (pin "1") (pinfunction "1_1") (pintype "passive"))
    )
    (net (code "29") (name "Net-(J2-Pad2)") (class "Default")
      (node (ref "J2") (pin "2") (pinfunction "2_2") (pintype "passive"))
      (node (ref "L2") (pin "2") (pinfunction "2_2") (pintype "passive"))
      (node (ref "P2") (pin "2") (pinfunction "2_2") (pintype "passive"))
    )
    (net (code "30") (name "Net-(J2-Pad3)") (class "Default")
      (node (ref "J2") (pin "3") (pinfunction "3_3") (pintype "passive"))
      (node (ref "L2") (pin "1") (pinfunction "1_1") (pintype "passive"))
      (node (ref "P2") (pin "3") (pinfunction "3_3") (pintype "passive"))
    )
    (net (code "31") (name "Net-(J3-Pad1)") (class "Default")
      (node (ref "J3") (pin "1") (pinfunction "1_1") (pintype "passive"))
      (node (ref "J3") (pin "G") (pinfunction "G_G") (pintype "passive"))
      (node (ref "P3") (pin "1") (pinfunction "1_1") (pintype "passive"))
      (node (ref "R6") (pin "2") (pinfunction "2_2") (pintype "passive"))
      (node (ref "R7") (pin "1") (pinfunction "1_1") (pintype "passive"))
      (node (ref "R8") (pin "2") (pinfunction "2_2") (pintype "passive"))
      (node (ref "R9") (pin "1") (pinfunction "1_1") (pintype "passive"))
    )
    (net (code "32") (name "Net-(J3-Pad2)") (class "Default")
      (node (ref "J3") (pin "2") (pinfunction "2_2") (pintype "passive"))
      (node (ref "L3") (pin "2") (pinfunction "2_2") (pintype "passive"))
      (node (ref "P3") (pin "2") (pinfunction "2_2") (pintype "passive"))
    )
    (net (code "33") (name "Net-(J3-Pad3)") (class "Default")
      (node (ref "J3") (pin "3") (pinfunction "3_3") (pintype "passive"))
      (node (ref "L3") (pin "1") (pinfunction "1_1") (pintype "passive"))
      (node (ref "P3") (pin "3") (pinfunction "3_3") (pintype "passive"))
    )
    (net (code "34") (name "Net-(J4-Pad2)") (class "Default")
      (node (ref "J4") (pin "2") (pinfunction "2_2") (pintype "passive"))
      (node (ref "L1") (pin "2") (pinfunction "2_2") (pintype "passive"))
      (node (ref "P4") (pin "2") (pinfunction "2_2") (pintype "passive"))
    )
    (net (code "35") (name "Net-(J4-Pad3)") (class "Default")
      (node (ref "J4") (pin "3") (pinfunction "3_3") (pintype "passive"))
      (node (ref "L1") (pin "1") (pinfunction "1_1") (pintype "passive"))
      (node (ref "P4") (pin "3") (pinfunction "3_3") (pintype "passive"))
    )
    (net (code "36") (name "Net-(R40-Pad1)") (class "Default")
      (node (ref "R40") (pin "1") (pinfunction "1_1") (pintype "passive"))
      (node (ref "R41") (pin "2") (pinfunction "2_2") (pintype "passive"))
    )
    (net (code "37") (name "Net-(U3-COM_A)") (class "Default")
      (node (ref "R3") (pin "2") (pinfunction "2_2") (pintype "passive"))
      (node (ref "U3") (pin "3") (pinfunction "COM_A_3") (pintype "passive"))
    )
    (net (code "38") (name "Net-(U3-COM_B)") (class "Default")
      (node (ref "R7") (pin "2") (pinfunction "2_2") (pintype "passive"))
      (node (ref "U3") (pin "6") (pinfunction "COM_B_6") (pintype "passive"))
    )
    (net (code "39") (name "Net-(U3-IN+A)") (class "Default")
      (node (ref "C5") (pin "2") (pinfunction "2_2") (pintype "passive"))
      (node (ref "U3") (pin "2") (pinfunction "IN+A_2") (pintype "passive"))
    )
    (net (code "40") (name "Net-(U3-IN+_B)") (class "Default")
      (node (ref "C8") (pin "2") (pinfunction "2_2") (pintype "passive"))
      (node (ref "U3") (pin "7") (pinfunction "IN+_B_7") (pintype "passive"))
    )
    (net (code "41") (name "Net-(U3-IN-_A)") (class "Default")
      (node (ref "C6") (pin "2") (pinfunction "2_2") (pintype "passive"))
      (node (ref "U3") (pin "4") (pinfunction "IN-_A_4") (pintype "passive"))
    )
    (net (code "42") (name "Net-(U3-IN-_B)") (class "Default")
      (node (ref "C9") (pin "2") (pinfunction "2_2") (pintype "passive"))
      (node (ref "U3") (pin "5") (pinfunction "IN-_B_5") (pintype "passive"))
    )
    (net (code "43") (name "Net-(U3-OUT_A)") (class "Default")
      (node (ref "R37") (pin "1") (pinfunction "1_1") (pintype "passive"))
      (node (ref "U3") (pin "13") (pinfunction "OUT_A_13") (pintype "passive"))
    )
    (net (code "44") (name "Net-(U3-OUT_B)") (class "Default")
      (node (ref "R38") (pin "1") (pinfunction "1_1") (pintype "passive"))
      (node (ref "U3") (pin "8") (pinfunction "OUT_B_8") (pintype "passive"))
    )
    (net (code "45") (name "Net-(U4-BFRAME)") (class "Default")
      (node (ref "TP10") (pin "1") (pinfunction "1_1") (pintype "passive"))
      (node (ref "U4") (pin "18") (pinfunction "BFRAME_18") (pintype "output"))
    )
    (net (code "46") (name "Net-(U4-CKSEL)") (class "Default")
      (node (ref "R10") (pin "1") (pinfunction "1_1") (pintype "passive"))
      (node (ref "U4") (pin "28") (pinfunction "CKSEL_28") (pintype "input"))
    )
    (net (code "47") (name "Net-(U4-CLKST)") (class "Default")
      (node (ref "TP5") (pin "1") (pinfunction "1_1") (pintype "passive"))
      (node (ref "U4") (pin "9") (pinfunction "CLKST_9") (pintype "output"))
    )
    (net (code "48") (name "Net-(U4-COUT)") (class "Default")
      (node (ref "TP8") (pin "1") (pinfunction "1_1") (pintype "passive"))
      (node (ref "U4") (pin "15") (pinfunction "COUT_15") (pintype "output"))
    )
    (net (code "49") (name "Net-(U4-EMPH)") (class "Default")
      (node (ref "TP12") (pin "1") (pinfunction "1_1") (pintype "passive"))
      (node (ref "U4") (pin "17") (pinfunction "EMPH_17") (pintype "output"))
    )
    (net (code "50") (name "Net-(U4-FILT)") (class "Default")
      (node (ref "C13") (pin "2") (pinfunction "2_2") (pintype "passive"))
      (node (ref "R12") (pin "2") (pinfunction "2_2") (pintype "passive"))
      (node (ref "U4") (pin "22") (pinfunction "FILT_22") (pintype "passive"))
    )
    (net (code "51") (name "Net-(U4-FSOUT0)") (class "Default")
      (node (ref "TP1") (pin "1") (pinfunction "1_1") (pintype "passive"))
      (node (ref "U4") (pin "2") (pinfunction "FSOUT0_2") (pintype "output"))
    )
    (net (code "52") (name "Net-(U4-FSOUT1)") (class "Default")
      (node (ref "TP2") (pin "1") (pinfunction "1_1") (pintype "passive"))
      (node (ref "U4") (pin "3") (pinfunction "FSOUT1_3") (pintype "output"))
    )
    (net (code "53") (name "Net-(U4-RXIN)") (class "Default")
      (node (ref "U4") (pin "20") (pinfunction "RXIN_20") (pintype "input"))
      (node (ref "U5") (pin "1") (pinfunction "RO_1") (pintype "tri_state"))
    )
    (net (code "54") (name "Net-(U4-UOUT)") (class "Default")
      (node (ref "TP9") (pin "1") (pinfunction "1_1") (pintype "passive"))
      (node (ref "U4") (pin "16") (pinfunction "UOUT_16") (pintype "output"))
    )
    (net (code "55") (name "Net-(U4-XTI)") (class "Default")
      (node (ref "C10") (pin "2") (pinfunction "2_2") (pintype "passive"))
      (node (ref "U4") (pin "8") (pinfunction "XTI_8") (pintype "input"))
      (node (ref "Y1") (pin "1") (pinfunction "OSC1_1") (pintype "passive"))
    )
    (net (code "56") (name "Net-(U4-XTO)") (class "Default")
      (node (ref "R11") (pin "2") (pinfunction "2_2") (pintype "passive"))
      (node (ref "U4") (pin "7") (pinfunction "XTO_7") (pintype "passive"))
    )
    (net (code "57") (name "Net-(U4-~{AUDIO})") (class "Default")
      (node (ref "TP13") (pin "1") (pinfunction "1_1") (pintype "passive"))
      (node (ref "U4") (pin "1") (pinfunction "~{AUDIO}_1") (pintype "output"))
    )
    (net (code "58") (name "Net-(U4-~{RST})") (class "Default")
      (node (ref "TP11") (pin "1") (pinfunction "1_1") (pintype "passive"))
      (node (ref "U4") (pin "21") (pinfunction "~{RST}_21") (pintype "input"))
    )
    (net (code "59") (name "Net-(U5-A)") (class "Default")
      (node (ref "R14") (pin "2") (pinfunction "2_2") (pintype "passive"))
      (node (ref "TR1") (pin "6") (pinfunction "6_6") (pintype "passive"))
      (node (ref "U5") (pin "6") (pinfunction "A_6") (pintype "bidirectional"))
    )
    (net (code "60") (name "Net-(U5-B)") (class "Default")
      (node (ref "R13") (pin "2") (pinfunction "2_2") (pintype "passive"))
      (node (ref "TR1") (pin "5") (pinfunction "5_5") (pintype "passive"))
      (node (ref "U5") (pin "7") (pinfunction "B_7") (pintype "bidirectional"))
    )
    (net (code "61") (name "Net-(U10-INA)") (class "Default")
      (node (ref "C36") (pin "2") (pinfunction "2_2") (pintype "passive"))
      (node (ref "U10") (pin "3") (pinfunction "INA_3") (pintype "passive"))
    )
    (net (code "62") (name "Net-(U10-INB)") (class "Default")
      (node (ref "C37") (pin "2") (pinfunction "2_2") (pintype "passive"))
      (node (ref "U10") (pin "8") (pinfunction "INB_8") (pintype "passive"))
    )
    (net (code "63") (name "Net-(U10-INT)") (class "Default")
      (node (ref "C38") (pin "2") (pinfunction "2_2") (pintype "passive"))
      (node (ref "U10") (pin "4") (pinfunction "INT_4") (pintype "passive"))
    )
    (net (code "64") (name "Net-(U10-SENSE)") (class "Default")
      (node (ref "R40") (pin "2") (pinfunction "2_2") (pintype "passive"))
      (node (ref "U10") (pin "6") (pinfunction "SENSE_6") (pintype "passive"))
    )
    (net (code "65") (name "Net-(U10-SW)") (class "Default")
      (node (ref "TP26") (pin "1") (pinfunction "1_1") (pintype "passive"))
      (node (ref "U10") (pin "7") (pinfunction "SW_7") (pintype "passive"))
    )
    (net (code "66") (name "Net-(U10-VREF)") (class "Default")
      (node (ref "C35") (pin "2") (pinfunction "2_2") (pintype "passive"))
      (node (ref "U10") (pin "5") (pinfunction "VREF_5") (pintype "passive"))
    )
    (net (code "67") (name "Net-(Y1-OSC2)") (class "Default")
      (node (ref "C11") (pin "2") (pinfunction "2_2") (pintype "passive"))
      (node (ref "R11") (pin "1") (pinfunction "1_1") (pintype "passive"))
      (node (ref "Y1") (pin "3") (pinfunction "OSC2_3") (pintype "passive"))
    )
    (net (code "68") (name "VCC") (class "Default")
      (node (ref "C4") (pin "2") (pinfunction "2_2") (pintype "passive"))
      (node (ref "U3") (pin "1") (pinfunction "VCC_1") (pintype "passive"))
    )
    (net (code "69") (name "VEE") (class "Default")
      (node (ref "C7") (pin "2") (pinfunction "2_2") (pintype "passive"))
      (node (ref "U3") (pin "14") (pinfunction "VEE_14") (pintype "passive"))
    )
    (net (code "70") (name "unconnected-(TR1-Pad3)") (class "Default")
      (node (ref "TR1") (pin "3") (pinfunction "3_3") (pintype "passive"))
    )
    (net (code "71") (name "unconnected-(U3-VMID_(In)-Pad11)") (class "Default")
      (node (ref "U3") (pin "11") (pinfunction "VMID_(In)_11") (pintype "passive"))
    )
    (net (code "72") (name "unconnected-(U3-VMID_(Out)-Pad10)") (class "Default")
      (node (ref "U3") (pin "10") (pinfunction "VMID_(Out)_10") (pintype "passive"))
    )
    (net (code "73") (name "unconnected-(U4-RSV-Pad19)") (class "Default")
      (node (ref "U4") (pin "19") (pinfunction "RSV_19") (pintype "power_in"))
    )
    (net (code "74") (name "unconnected-(U5-DI-Pad4)") (class "Default")
      (node (ref "U5") (pin "4") (pinfunction "DI_4") (pintype "input+no_connect"))
    )
  )
)
